# BMS_Carrier_-_Battery_Relay_Controls.net
KiCad netlist of a schematic drawn in Altium Designer
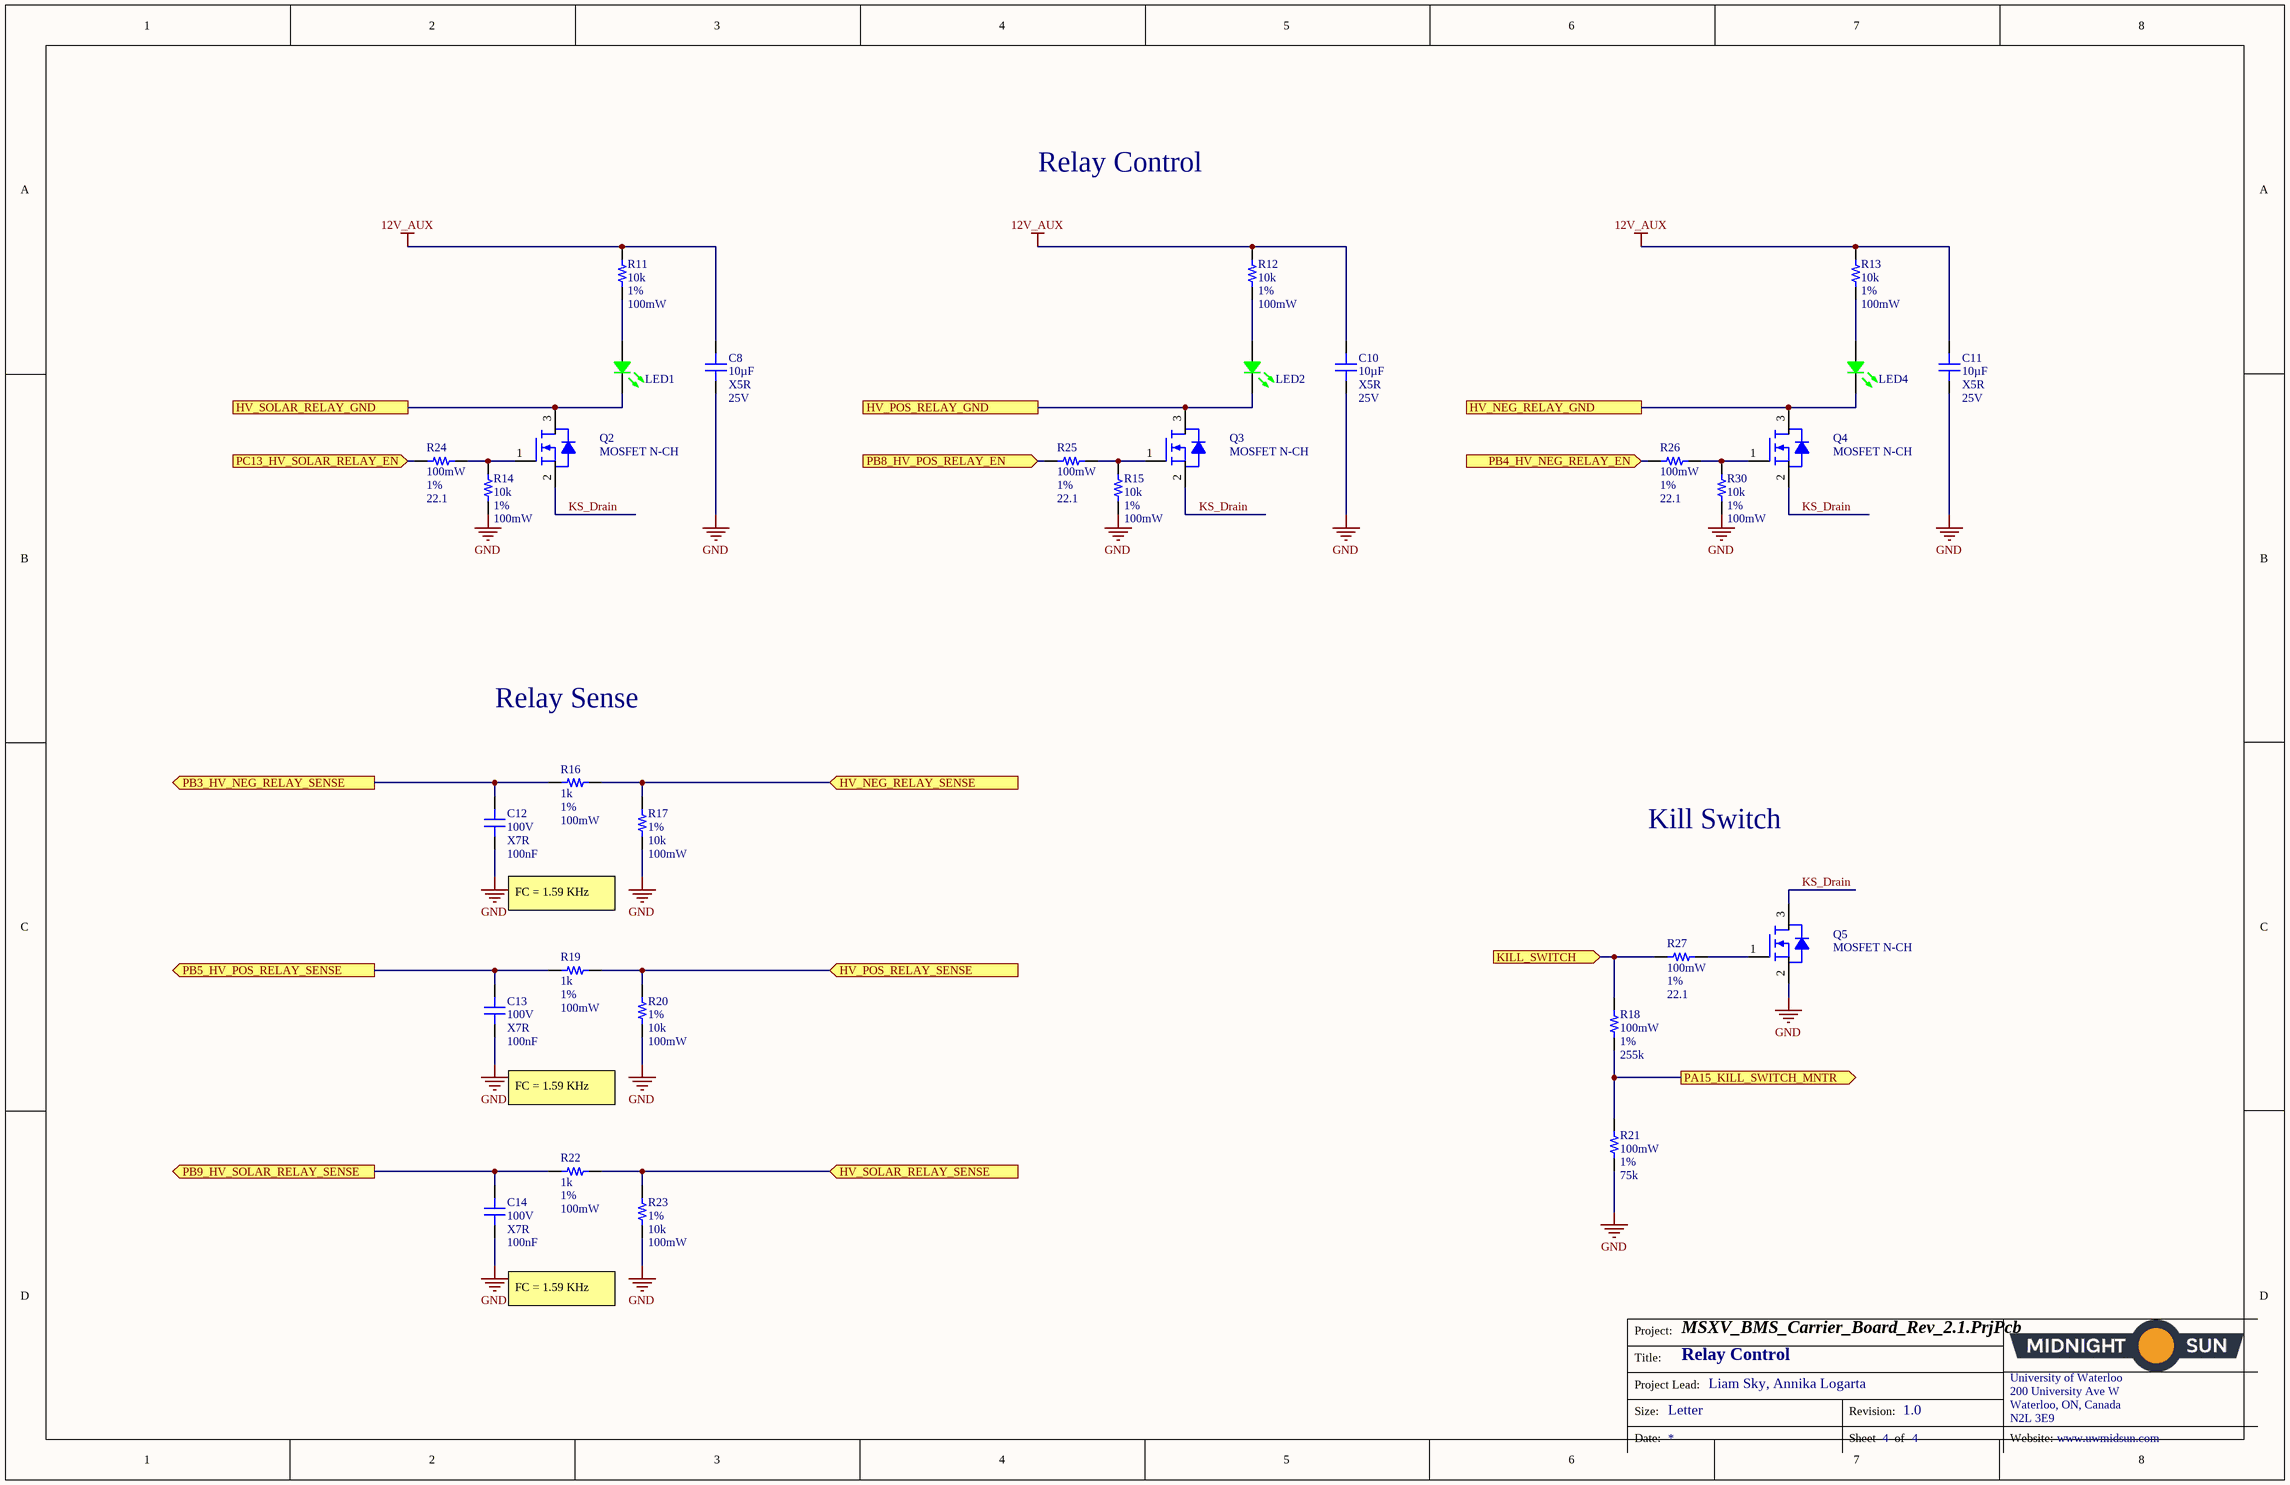
[diagram p0: BMS Carrier - Battery Relay Controls.SchDoc]

(export (version "E")
  (design (tool "Eeschema 10.0.6"))
  (components
    (comp (ref "C8")
      (value "CAP CER 10UF 25V 20% X5R 0603")
      (footprint "CAP 0603_1608")
      (description "10µF ±20% 25V Ceramic Capacitor X5R 0603 (1608 Metric)")
      (fields
        (field (name "CAPACITANCE") "10µF")
        (field (name "TOLERANCE") "20%")
        (field (name "DIELECTRIC CODE") "X5R")
        (field (name "VOLTAGE RATING") "25V")
      )
      (libsource (lib "Midnight Sun") (part "Capacitor"))
    )
    (comp (ref "C10")
      (value "CAP CER 10UF 25V 20% X5R 0603")
      (footprint "CAP 0603_1608")
      (description "10µF ±20% 25V Ceramic Capacitor X5R 0603 (1608 Metric)")
      (fields
        (field (name "CAPACITANCE") "10µF")
        (field (name "TOLERANCE") "20%")
        (field (name "DIELECTRIC CODE") "X5R")
        (field (name "VOLTAGE RATING") "25V")
      )
      (libsource (lib "Midnight Sun") (part "Capacitor"))
    )
    (comp (ref "C11")
      (value "CAP CER 10UF 25V 20% X5R 0603")
      (footprint "CAP 0603_1608")
      (description "10µF ±20% 25V Ceramic Capacitor X5R 0603 (1608 Metric)")
      (fields
        (field (name "CAPACITANCE") "10µF")
        (field (name "TOLERANCE") "20%")
        (field (name "DIELECTRIC CODE") "X5R")
        (field (name "VOLTAGE RATING") "25V")
      )
      (libsource (lib "Midnight Sun") (part "Capacitor"))
    )
    (comp (ref "C12")
      (value "CAP CER 0.1UF 100V 10% X7R 0603")
      (footprint "CAP 0603_1608")
      (fields
        (field (name "VOLTAGE RATING") "100V")
        (field (name "TOLERANCE") "10%")
        (field (name "DIELECTRIC CODE") "X7R")
        (field (name "CAPACITANCE") "100nF")
      )
      (libsource (lib "Midnight Sun") (part "Capacitor"))
    )
    (comp (ref "C13")
      (value "CAP CER 0.1UF 100V 10% X7R 0603")
      (footprint "CAP 0603_1608")
      (fields
        (field (name "VOLTAGE RATING") "100V")
        (field (name "TOLERANCE") "10%")
        (field (name "DIELECTRIC CODE") "X7R")
        (field (name "CAPACITANCE") "100nF")
      )
      (libsource (lib "Midnight Sun") (part "Capacitor"))
    )
    (comp (ref "C14")
      (value "CAP CER 0.1UF 100V 10% X7R 0603")
      (footprint "CAP 0603_1608")
      (fields
        (field (name "VOLTAGE RATING") "100V")
        (field (name "TOLERANCE") "10%")
        (field (name "DIELECTRIC CODE") "X7R")
        (field (name "CAPACITANCE") "100nF")
      )
      (libsource (lib "Midnight Sun") (part "Capacitor"))
    )
    (comp (ref "LED1")
      (value "LED GREEN CLEAR 2V 0603")
      (footprint "LED 0603_1608")
      (description "Green 562nm LED Indication - Discrete 2V 0603 (1608 Metric)")
      (libsource (lib "Midnight Sun") (part "LED GREEN"))
    )
    (comp (ref "LED2")
      (value "LED GREEN CLEAR 2V 0603")
      (footprint "LED 0603_1608")
      (description "Green 562nm LED Indication - Discrete 2V 0603 (1608 Metric)")
      (libsource (lib "Midnight Sun") (part "LED GREEN"))
    )
    (comp (ref "LED4")
      (value "LED GREEN CLEAR 2V 0603")
      (footprint "LED 0603_1608")
      (description "Green 562nm LED Indication - Discrete 2V 0603 (1608 Metric)")
      (libsource (lib "Midnight Sun") (part "LED GREEN"))
    )
    (comp (ref "Q2")
      (value "MOSFET N-CH")
      (footprint "SOT 23-3")
      (description "N-Channel 30V 6.2A (Ta) 900mW (Ta) Surface Mount SOT-23")
      (fields (field (name "POWER") "900mW"))
      (libsource (lib "Midnight Sun") (part "MOSFET N-CH"))
    )
    (comp (ref "Q3")
      (value "MOSFET N-CH")
      (footprint "SOT 23-3")
      (description "N-Channel 30V 6.2A (Ta) 900mW (Ta) Surface Mount SOT-23")
      (fields (field (name "POWER") "900mW"))
      (libsource (lib "Midnight Sun") (part "MOSFET N-CH"))
    )
    (comp (ref "Q4")
      (value "MOSFET N-CH")
      (footprint "SOT 23-3")
      (description "N-Channel 30V 6.2A (Ta) 900mW (Ta) Surface Mount SOT-23")
      (fields (field (name "POWER") "900mW"))
      (libsource (lib "Midnight Sun") (part "MOSFET N-CH"))
    )
    (comp (ref "Q5")
      (value "MOSFET N-CH")
      (footprint "SOT 23-3")
      (description "N-Channel 30V 6.2A (Ta) 900mW (Ta) Surface Mount SOT-23")
      (fields (field (name "POWER") "900mW"))
      (libsource (lib "Midnight Sun") (part "MOSFET N-CH"))
    )
    (comp (ref "R11")
      (value "RES 10K OHM 1% 1/10W 0603")
      (footprint "RES 0603_1608")
      (description "10 ±1% 0.1W, 1/10W Chip Resistor 0603 (1608 Metric) Automotive AEC-Q200 Thick Film")
      (fields
        (field (name "RESISTANCE") "10k")
        (field (name "TOLERANCE") "1%")
        (field (name "POWER RATING") "100mW")
      )
      (libsource (lib "Midnight Sun") (part "Resistor"))
    )
    (comp (ref "R12")
      (value "RES 10K OHM 1% 1/10W 0603")
      (footprint "RES 0603_1608")
      (description "10 ±1% 0.1W, 1/10W Chip Resistor 0603 (1608 Metric) Automotive AEC-Q200 Thick Film")
      (fields
        (field (name "RESISTANCE") "10k")
        (field (name "TOLERANCE") "1%")
        (field (name "POWER RATING") "100mW")
      )
      (libsource (lib "Midnight Sun") (part "Resistor"))
    )
    (comp (ref "R13")
      (value "RES 10K OHM 1% 1/10W 0603")
      (footprint "RES 0603_1608")
      (description "10 ±1% 0.1W, 1/10W Chip Resistor 0603 (1608 Metric) Automotive AEC-Q200 Thick Film")
      (fields
        (field (name "RESISTANCE") "10k")
        (field (name "TOLERANCE") "1%")
        (field (name "POWER RATING") "100mW")
      )
      (libsource (lib "Midnight Sun") (part "Resistor"))
    )
    (comp (ref "R14")
      (value "RES 10K OHM 1% 1/10W 0603")
      (footprint "RES 0603_1608")
      (description "10 ±1% 0.1W, 1/10W Chip Resistor 0603 (1608 Metric) Automotive AEC-Q200 Thick Film")
      (fields
        (field (name "RESISTANCE") "10k")
        (field (name "TOLERANCE") "1%")
        (field (name "POWER RATING") "100mW")
      )
      (libsource (lib "Midnight Sun") (part "Resistor"))
    )
    (comp (ref "R15")
      (value "RES 10K OHM 1% 1/10W 0603")
      (footprint "RES 0603_1608")
      (description "10 ±1% 0.1W, 1/10W Chip Resistor 0603 (1608 Metric) Automotive AEC-Q200 Thick Film")
      (fields
        (field (name "RESISTANCE") "10k")
        (field (name "TOLERANCE") "1%")
        (field (name "POWER RATING") "100mW")
      )
      (libsource (lib "Midnight Sun") (part "Resistor"))
    )
    (comp (ref "R16")
      (value "RES 1K OHM 1% 1/10W 0603")
      (footprint "RES 0603_1608")
      (description "1 kOhms ±1% 0.1W, 1/10W Chip Resistor 0603 (1608 Metric) Moisture Resistant Thick Film")
      (fields
        (field (name "RESISTANCE") "1k")
        (field (name "TOLERANCE") "1%")
        (field (name "POWER RATING") "100mW")
      )
      (libsource (lib "Midnight Sun") (part "Resistor"))
    )
    (comp (ref "R17")
      (value "RES 10K OHM 1% 1/10W 0603")
      (footprint "RES 0603_1608")
      (description "10 ±1% 0.1W, 1/10W Chip Resistor 0603 (1608 Metric) Automotive AEC-Q200 Thick Film")
      (fields
        (field (name "TOLERANCE") "1%")
        (field (name "RESISTANCE") "10k")
        (field (name "POWER RATING") "100mW")
      )
      (libsource (lib "Midnight Sun") (part "Resistor"))
    )
    (comp (ref "R18")
      (value "RES 255K OHM 1% 1/10W 0603")
      (footprint "RES 0603_1608")
      (description "255k Ohm ±1% 0.1W, 1/10W Chip Resistor 0603 (1608 Metric) Moisture Resistant Thick Film")
      (fields
        (field (name "POWER RATING") "100mW")
        (field (name "TOLERANCE") "1%")
        (field (name "RESISTANCE") "255k")
      )
      (libsource (lib "Midnight Sun") (part "Resistor"))
    )
    (comp (ref "R19")
      (value "RES 1K OHM 1% 1/10W 0603")
      (footprint "RES 0603_1608")
      (description "1 kOhms ±1% 0.1W, 1/10W Chip Resistor 0603 (1608 Metric) Moisture Resistant Thick Film")
      (fields
        (field (name "RESISTANCE") "1k")
        (field (name "TOLERANCE") "1%")
        (field (name "POWER RATING") "100mW")
      )
      (libsource (lib "Midnight Sun") (part "Resistor"))
    )
    (comp (ref "R20")
      (value "RES 10K OHM 1% 1/10W 0603")
      (footprint "RES 0603_1608")
      (description "10 ±1% 0.1W, 1/10W Chip Resistor 0603 (1608 Metric) Automotive AEC-Q200 Thick Film")
      (fields
        (field (name "TOLERANCE") "1%")
        (field (name "RESISTANCE") "10k")
        (field (name "POWER RATING") "100mW")
      )
      (libsource (lib "Midnight Sun") (part "Resistor"))
    )
    (comp (ref "R21")
      (value "RES 75K OHM 1% 1/10W 0603")
      (footprint "RES 0603_1608")
      (fields
        (field (name "POWER RATING") "100mW")
        (field (name "TOLERANCE") "1%")
        (field (name "RESISTANCE") "75k")
      )
      (libsource (lib "Midnight Sun") (part "Resistor"))
    )
    (comp (ref "R22")
      (value "RES 1K OHM 1% 1/10W 0603")
      (footprint "RES 0603_1608")
      (description "1 kOhms ±1% 0.1W, 1/10W Chip Resistor 0603 (1608 Metric) Moisture Resistant Thick Film")
      (fields
        (field (name "RESISTANCE") "1k")
        (field (name "TOLERANCE") "1%")
        (field (name "POWER RATING") "100mW")
      )
      (libsource (lib "Midnight Sun") (part "Resistor"))
    )
    (comp (ref "R23")
      (value "RES 10K OHM 1% 1/10W 0603")
      (footprint "RES 0603_1608")
      (description "10 ±1% 0.1W, 1/10W Chip Resistor 0603 (1608 Metric) Automotive AEC-Q200 Thick Film")
      (fields
        (field (name "TOLERANCE") "1%")
        (field (name "RESISTANCE") "10k")
        (field (name "POWER RATING") "100mW")
      )
      (libsource (lib "Midnight Sun") (part "Resistor"))
    )
    (comp (ref "R24")
      (value "RES 22.1 OHM 1% 1/10W 0603")
      (footprint "RES 0603_1608")
      (fields
        (field (name "POWER RATING") "100mW")
        (field (name "TOLERANCE") "1%")
        (field (name "RESISTANCE") "22.1")
      )
      (libsource (lib "Midnight Sun") (part "Resistor"))
    )
    (comp (ref "R25")
      (value "RES 22.1 OHM 1% 1/10W 0603")
      (footprint "RES 0603_1608")
      (fields
        (field (name "POWER RATING") "100mW")
        (field (name "TOLERANCE") "1%")
        (field (name "RESISTANCE") "22.1")
      )
      (libsource (lib "Midnight Sun") (part "Resistor"))
    )
    (comp (ref "R26")
      (value "RES 22.1 OHM 1% 1/10W 0603")
      (footprint "RES 0603_1608")
      (fields
        (field (name "POWER RATING") "100mW")
        (field (name "TOLERANCE") "1%")
        (field (name "RESISTANCE") "22.1")
      )
      (libsource (lib "Midnight Sun") (part "Resistor"))
    )
    (comp (ref "R27")
      (value "RES 22.1 OHM 1% 1/10W 0603")
      (footprint "RES 0603_1608")
      (fields
        (field (name "POWER RATING") "100mW")
        (field (name "TOLERANCE") "1%")
        (field (name "RESISTANCE") "22.1")
      )
      (libsource (lib "Midnight Sun") (part "Resistor"))
    )
    (comp (ref "R30")
      (value "RES 10K OHM 1% 1/10W 0603")
      (footprint "RES 0603_1608")
      (description "10 ±1% 0.1W, 1/10W Chip Resistor 0603 (1608 Metric) Automotive AEC-Q200 Thick Film")
      (fields
        (field (name "RESISTANCE") "10k")
        (field (name "TOLERANCE") "1%")
        (field (name "POWER RATING") "100mW")
      )
      (libsource (lib "Midnight Sun") (part "Resistor"))
    )
  )
  (nets
    (net (code "1") (name "/HV_NEG_RELAY_GND") (class "Default")
      (node (ref "LED4") (pin "1") (pinfunction "1_1") (pintype "passive"))
      (node (ref "Q4") (pin "3") (pinfunction "D_3") (pintype "passive"))
    )
    (net (code "2") (name "/HV_NEG_RELAY_SENSE") (class "Default")
      (node (ref "R16") (pin "2") (pinfunction "2_2") (pintype "passive"))
      (node (ref "R17") (pin "2") (pinfunction "2_2") (pintype "passive"))
    )
    (net (code "3") (name "/HV_POS_RELAY_GND") (class "Default")
      (node (ref "LED2") (pin "1") (pinfunction "1_1") (pintype "passive"))
      (node (ref "Q3") (pin "3") (pinfunction "D_3") (pintype "passive"))
    )
    (net (code "4") (name "/HV_POS_RELAY_SENSE") (class "Default")
      (node (ref "R19") (pin "2") (pinfunction "2_2") (pintype "passive"))
      (node (ref "R20") (pin "2") (pinfunction "2_2") (pintype "passive"))
    )
    (net (code "5") (name "/HV_SOLAR_RELAY_GND") (class "Default")
      (node (ref "LED1") (pin "1") (pinfunction "1_1") (pintype "passive"))
      (node (ref "Q2") (pin "3") (pinfunction "D_3") (pintype "passive"))
    )
    (net (code "6") (name "/HV_SOLAR_RELAY_SENSE") (class "Default")
      (node (ref "R22") (pin "2") (pinfunction "2_2") (pintype "passive"))
      (node (ref "R23") (pin "2") (pinfunction "2_2") (pintype "passive"))
    )
    (net (code "7") (name "/KILL_SWITCH") (class "Default")
      (node (ref "R18") (pin "2") (pinfunction "2_2") (pintype "passive"))
      (node (ref "R27") (pin "1") (pinfunction "1_1") (pintype "passive"))
    )
    (net (code "8") (name "/KS_Drain") (class "Default")
      (node (ref "Q2") (pin "2") (pinfunction "S_2") (pintype "passive"))
      (node (ref "Q3") (pin "2") (pinfunction "S_2") (pintype "passive"))
      (node (ref "Q4") (pin "2") (pinfunction "S_2") (pintype "passive"))
      (node (ref "Q5") (pin "3") (pinfunction "D_3") (pintype "passive"))
    )
    (net (code "9") (name "/PA15_KILL_SWITCH_MNTR") (class "Default")
      (node (ref "R18") (pin "1") (pinfunction "1_1") (pintype "passive"))
      (node (ref "R21") (pin "2") (pinfunction "2_2") (pintype "passive"))
    )
    (net (code "10") (name "/PB3_HV_NEG_RELAY_SENSE") (class "Default")
      (node (ref "C12") (pin "2") (pinfunction "2_2") (pintype "passive"))
      (node (ref "R16") (pin "1") (pinfunction "1_1") (pintype "passive"))
    )
    (net (code "11") (name "/PB4_HV_NEG_RELAY_EN") (class "Default")
      (node (ref "R26") (pin "1") (pinfunction "1_1") (pintype "passive"))
    )
    (net (code "12") (name "/PB5_HV_POS_RELAY_SENSE") (class "Default")
      (node (ref "C13") (pin "2") (pinfunction "2_2") (pintype "passive"))
      (node (ref "R19") (pin "1") (pinfunction "1_1") (pintype "passive"))
    )
    (net (code "13") (name "/PB8_HV_POS_RELAY_EN") (class "Default")
      (node (ref "R25") (pin "1") (pinfunction "1_1") (pintype "passive"))
    )
    (net (code "14") (name "/PB9_HV_SOLAR_RELAY_SENSE") (class "Default")
      (node (ref "C14") (pin "2") (pinfunction "2_2") (pintype "passive"))
      (node (ref "R22") (pin "1") (pinfunction "1_1") (pintype "passive"))
    )
    (net (code "15") (name "/PC13_HV_SOLAR_RELAY_EN") (class "Default")
      (node (ref "R24") (pin "1") (pinfunction "1_1") (pintype "passive"))
    )
    (net (code "16") (name "12V_AUX") (class "Default")
      (node (ref "C10") (pin "2") (pinfunction "2_2") (pintype "passive"))
      (node (ref "C11") (pin "2") (pinfunction "2_2") (pintype "passive"))
      (node (ref "C8") (pin "2") (pinfunction "2_2") (pintype "passive"))
      (node (ref "R11") (pin "2") (pinfunction "2_2") (pintype "passive"))
      (node (ref "R12") (pin "2") (pinfunction "2_2") (pintype "passive"))
      (node (ref "R13") (pin "2") (pinfunction "2_2") (pintype "passive"))
    )
    (net (code "17") (name "GND") (class "Default")
      (node (ref "C10") (pin "1") (pinfunction "1_1") (pintype "passive"))
      (node (ref "C11") (pin "1") (pinfunction "1_1") (pintype "passive"))
      (node (ref "C12") (pin "1") (pinfunction "1_1") (pintype "passive"))
      (node (ref "C13") (pin "1") (pinfunction "1_1") (pintype "passive"))
      (node (ref "C14") (pin "1") (pinfunction "1_1") (pintype "passive"))
      (node (ref "C8") (pin "1") (pinfunction "1_1") (pintype "passive"))
      (node (ref "Q5") (pin "2") (pinfunction "S_2") (pintype "passive"))
      (node (ref "R14") (pin "1") (pinfunction "1_1") (pintype "passive"))
      (node (ref "R15") (pin "1") (pinfunction "1_1") (pintype "passive"))
      (node (ref "R17") (pin "1") (pinfunction "1_1") (pintype "passive"))
      (node (ref "R20") (pin "1") (pinfunction "1_1") (pintype "passive"))
      (node (ref "R21") (pin "1") (pinfunction "1_1") (pintype "passive"))
      (node (ref "R23") (pin "1") (pinfunction "1_1") (pintype "passive"))
      (node (ref "R30") (pin "1") (pinfunction "1_1") (pintype "passive"))
    )
    (net (code "18") (name "Net-(LED1-Pad2)") (class "Default")
      (node (ref "LED1") (pin "2") (pinfunction "2_2") (pintype "passive"))
      (node (ref "R11") (pin "1") (pinfunction "1_1") (pintype "passive"))
    )
    (net (code "19") (name "Net-(LED2-Pad2)") (class "Default")
      (node (ref "LED2") (pin "2") (pinfunction "2_2") (pintype "passive"))
      (node (ref "R12") (pin "1") (pinfunction "1_1") (pintype "passive"))
    )
    (net (code "20") (name "Net-(LED4-Pad2)") (class "Default")
      (node (ref "LED4") (pin "2") (pinfunction "2_2") (pintype "passive"))
      (node (ref "R13") (pin "1") (pinfunction "1_1") (pintype "passive"))
    )
    (net (code "21") (name "Net-(Q2-G)") (class "Default")
      (node (ref "Q2") (pin "1") (pinfunction "G_1") (pintype "passive"))
      (node (ref "R14") (pin "2") (pinfunction "2_2") (pintype "passive"))
      (node (ref "R24") (pin "2") (pinfunction "2_2") (pintype "passive"))
    )
    (net (code "22") (name "Net-(Q3-G)") (class "Default")
      (node (ref "Q3") (pin "1") (pinfunction "G_1") (pintype "passive"))
      (node (ref "R15") (pin "2") (pinfunction "2_2") (pintype "passive"))
      (node (ref "R25") (pin "2") (pinfunction "2_2") (pintype "passive"))
    )
    (net (code "23") (name "Net-(Q4-G)") (class "Default")
      (node (ref "Q4") (pin "1") (pinfunction "G_1") (pintype "passive"))
      (node (ref "R26") (pin "2") (pinfunction "2_2") (pintype "passive"))
      (node (ref "R30") (pin "2") (pinfunction "2_2") (pintype "passive"))
    )
    (net (code "24") (name "Net-(Q5-G)") (class "Default")
      (node (ref "Q5") (pin "1") (pinfunction "G_1") (pintype "passive"))
      (node (ref "R27") (pin "2") (pinfunction "2_2") (pintype "passive"))
    )
  )
)
